# HUB_V1_3_22_0712.net
KiCad netlist of a schematic drawn in Altium Designer
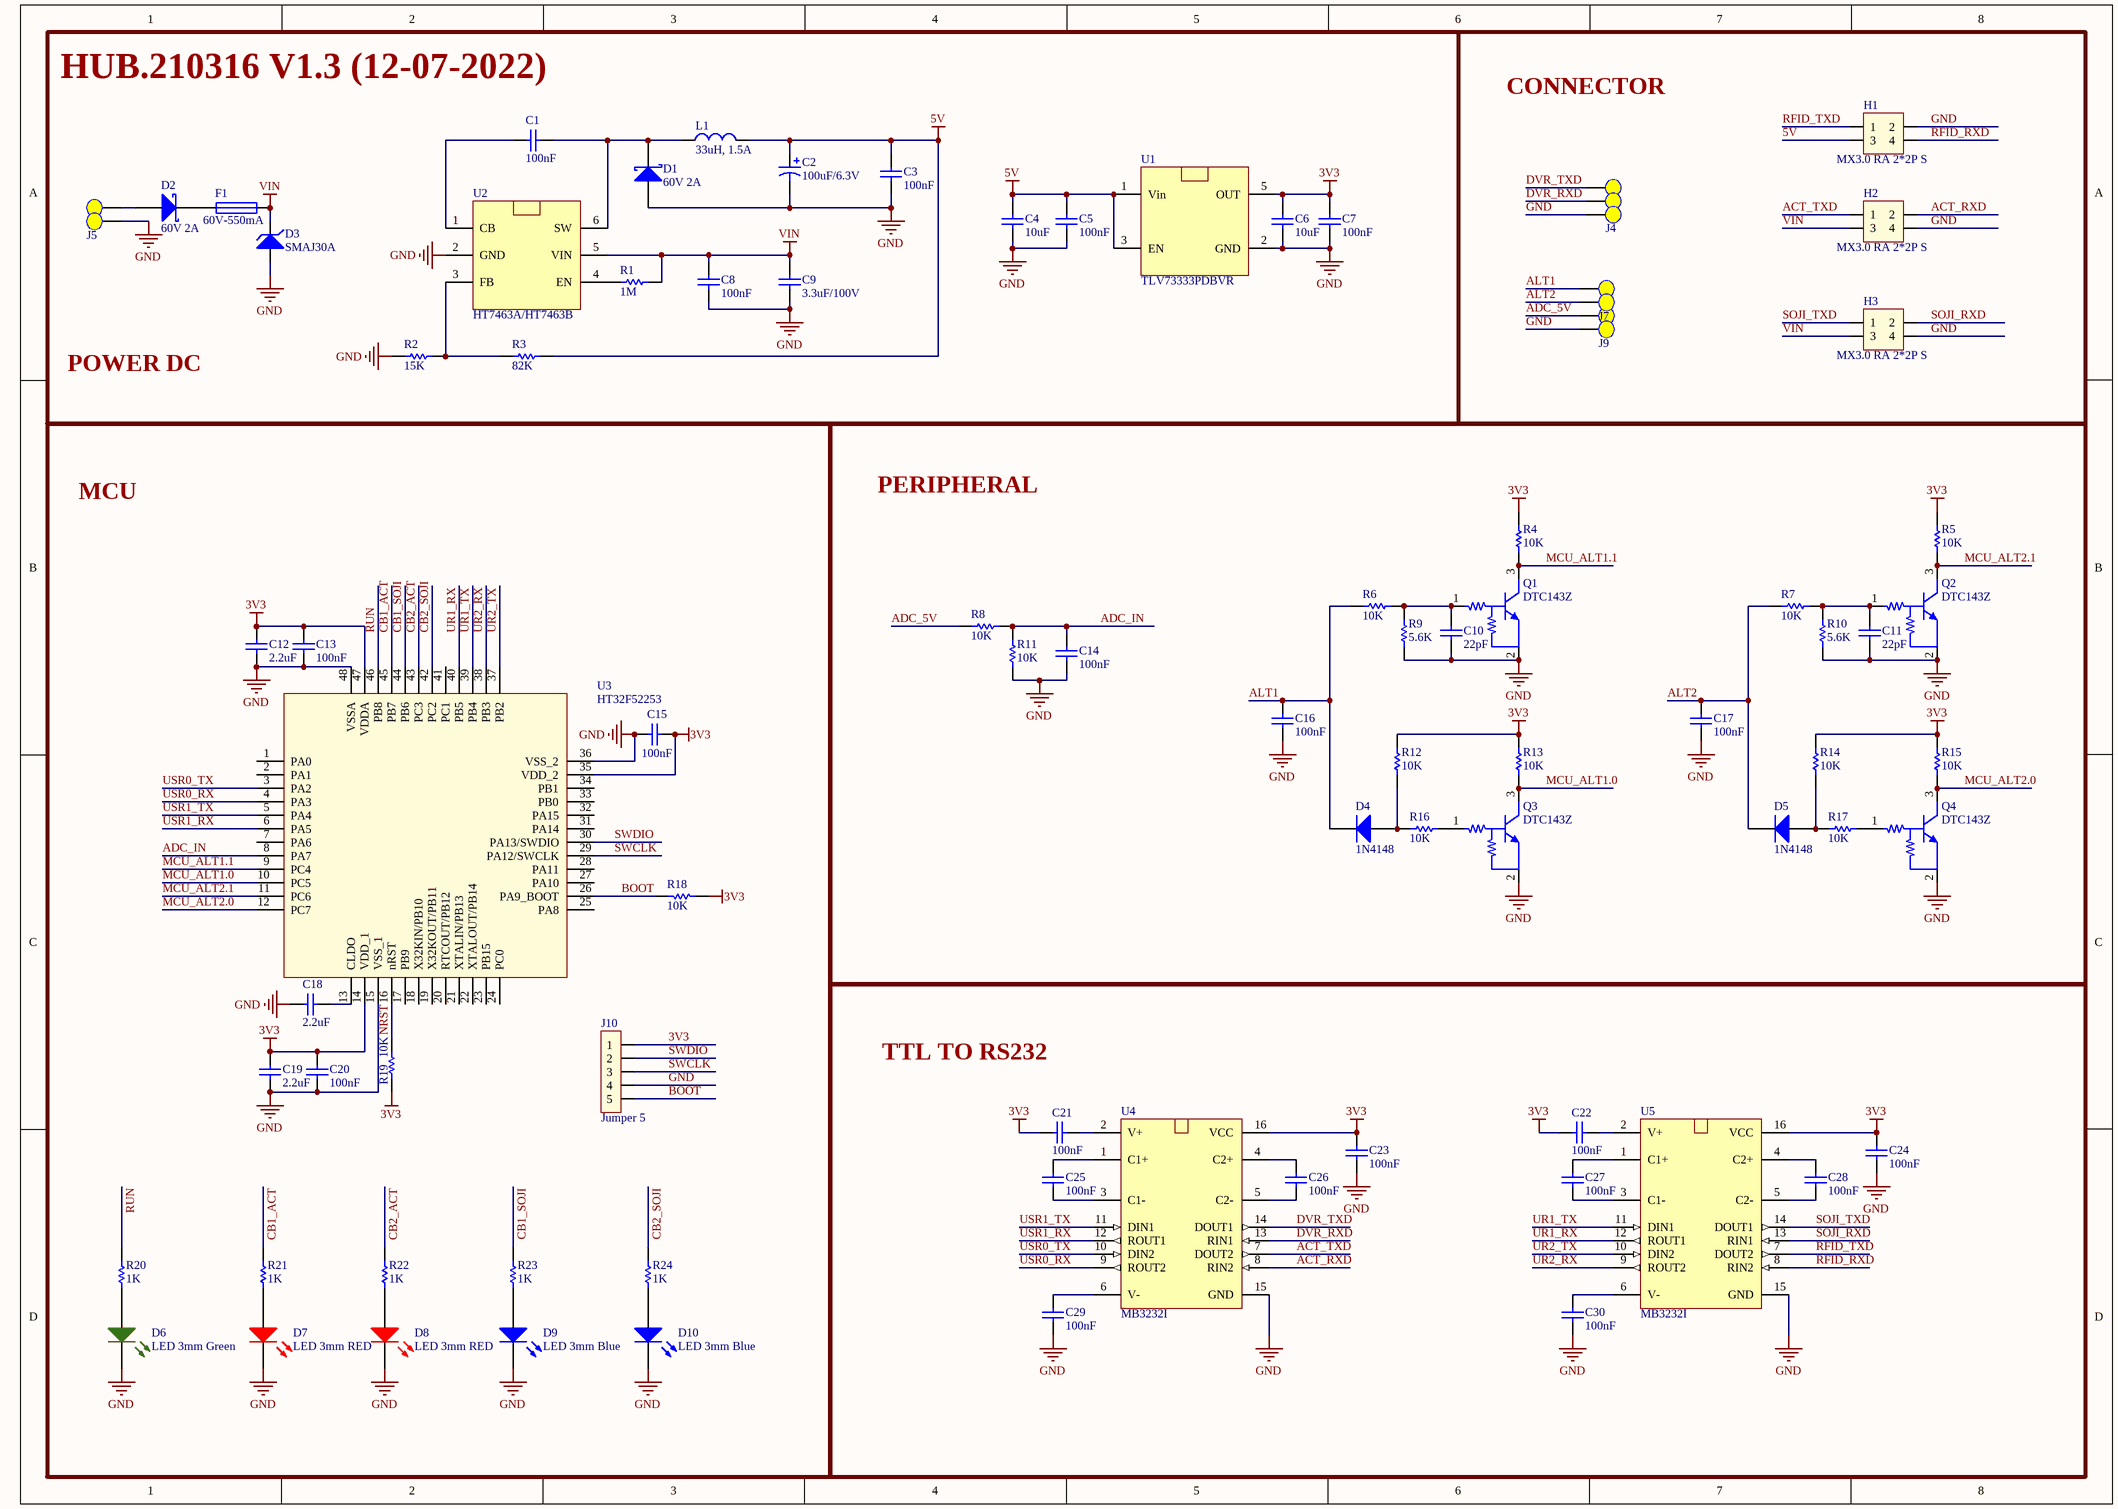
[diagram p0: HUB V1.3.22.0712.SchDoc]

(export (version "E")
  (design (tool "Eeschema 10.0.6"))
  (components
    (comp (ref "C1")
      (value "100nF")
      (footprint "0603 - C")
      (description "CAP CER 100nF 50V C0G/NP0 0603")
      (fields (field (name "MPN") "CL10C104JB8NNNC") (field (name "MFR") "SAMSUNG"))
      (libsource (lib "Library_Chip1") (part "Cap 0603 100nF"))
    )
    (comp (ref "C2")
      (value "100uF/6.3V")
      (footprint "3528 - TANTALUM")
      (description "CAP TANT 100UF 6.3V 10% 1411")
      (fields (field (name "MPN") "T491B107K006AT") (field (name "MFR") "Kemet"))
      (libsource (lib "Library_Chip1") (part "Cap Tan 3528 100uF/6.3V"))
    )
    (comp (ref "C3")
      (value "100nF")
      (footprint "0603 - C")
      (description "CAP CER 100nF 50V C0G/NP0 0603")
      (fields (field (name "MPN") "CL10C104JB8NNNC") (field (name "MFR") "SAMSUNG"))
      (libsource (lib "Library_Chip1") (part "Cap 0603 100nF"))
    )
    (comp (ref "C4")
      (value "10uF")
      (footprint "0603 - C")
      (description "CAP CER 10UF 16V X5R 0603")
      (fields (field (name "MPN") "EMK107BBJ106MA-T") (field (name "MFR") "Yageo"))
      (libsource (lib "Library_Chip") (part "Cap 0603 10uF"))
    )
    (comp (ref "C5")
      (value "100nF")
      (footprint "0603 - C")
      (description "CAP CER 100nF 50V C0G/NP0 0603")
      (fields (field (name "MPN") "CL10C104JB8NNNC") (field (name "MFR") "SAMSUNG"))
      (libsource (lib "Library_Chip") (part "Cap 0603 100nF"))
    )
    (comp (ref "C6")
      (value "10uF")
      (footprint "0603 - C")
      (description "CAP CER 10UF 16V X5R 0603")
      (fields (field (name "MPN") "EMK107BBJ106MA-T") (field (name "MFR") "Yageo"))
      (libsource (lib "Library_Chip") (part "Cap 0603 10uF"))
    )
    (comp (ref "C7")
      (value "100nF")
      (footprint "0603 - C")
      (description "CAP CER 100nF 50V C0G/NP0 0603")
      (fields (field (name "MPN") "CL10C104JB8NNNC") (field (name "MFR") "SAMSUNG"))
      (libsource (lib "Library_Chip") (part "Cap 0603 100nF"))
    )
    (comp (ref "C8")
      (value "100nF")
      (footprint "0603 - C")
      (description "CAP CER 100nF 50V C0G/NP0 0603")
      (fields (field (name "MPN") "CL10C104JB8NNNC") (field (name "MFR") "SAMSUNG"))
      (libsource (lib "Library_Chip1") (part "Cap 0603 100nF"))
    )
    (comp (ref "C9")
      (value "3.3uF/100V")
      (footprint "1210 - C")
      (description "CAP CER 3.3UF 100V X7S 1210")
      (fields (field (name "MPN") "C3225X7S2A335M200AB") (field (name "MFR") "TDK Corporation"))
      (libsource (lib "Library_Chip1") (part "Cap 1210 3.3uF"))
    )
    (comp (ref "C10")
      (value "22pF")
      (footprint "0603 - C")
      (description "CAP CER 22PF 50V C0G/NP0 0603")
      (fields (field (name "MPN") "CL10C220JB8NNNC") (field (name "MFR") "SAMSUNG"))
      (libsource (lib "Library_Chip1") (part "Cap 0603 22pF"))
    )
    (comp (ref "C11")
      (value "22pF")
      (footprint "0603 - C")
      (description "CAP CER 22PF 50V C0G/NP0 0603")
      (fields (field (name "MPN") "CL10C220JB8NNNC") (field (name "MFR") "SAMSUNG"))
      (libsource (lib "Library_Chip1") (part "Cap 0603 22pF"))
    )
    (comp (ref "C12")
      (value "2.2uF")
      (footprint "0603 - C")
      (description "CAP CER 2.2UF 50V X5R 0603")
      (fields (field (name "MFR") "Murata Electronics") (field (name "MPN") "GRM188R61H225KE11J"))
      (libsource (lib "Library_Chip1") (part "Cap 0603 2.2uF"))
    )
    (comp (ref "C13")
      (value "100nF")
      (footprint "0603 - C")
      (description "CAP CER 100nF 50V C0G/NP0 0603")
      (fields (field (name "MPN") "CL10C104JB8NNNC") (field (name "MFR") "SAMSUNG"))
      (libsource (lib "Library_Chip1") (part "Cap 0603 100nF"))
    )
    (comp (ref "C14")
      (value "100nF")
      (footprint "0603 - C")
      (description "CAP CER 100nF 50V C0G/NP0 0603")
      (fields (field (name "MPN") "CL10C104JB8NNNC") (field (name "MFR") "SAMSUNG"))
      (libsource (lib "Library_Chip") (part "Cap 0603 100nF"))
    )
    (comp (ref "C15")
      (value "100nF")
      (footprint "0603 - C")
      (description "CAP CER 100nF 50V C0G/NP0 0603")
      (fields (field (name "MPN") "CL10C104JB8NNNC") (field (name "MFR") "SAMSUNG"))
      (libsource (lib "Library_Chip1") (part "Cap 0603 100nF"))
    )
    (comp (ref "C16")
      (value "100nF")
      (footprint "0603 - C")
      (description "CAP CER 100nF 50V C0G/NP0 0603")
      (fields (field (name "MPN") "CL10C104JB8NNNC") (field (name "MFR") "SAMSUNG"))
      (libsource (lib "Library_Chip1") (part "Cap 0603 100nF"))
    )
    (comp (ref "C17")
      (value "100nF")
      (footprint "0603 - C")
      (description "CAP CER 100nF 50V C0G/NP0 0603")
      (fields (field (name "MPN") "CL10C104JB8NNNC") (field (name "MFR") "SAMSUNG"))
      (libsource (lib "Library_Chip1") (part "Cap 0603 100nF"))
    )
    (comp (ref "C18")
      (value "2.2uF")
      (footprint "0603 - C")
      (description "CAP CER 2.2UF 50V X5R 0603")
      (fields (field (name "MFR") "Murata Electronics") (field (name "MPN") "GRM188R61H225KE11J"))
      (libsource (lib "Library_Chip1") (part "Cap 0603 2.2uF"))
    )
    (comp (ref "C19")
      (value "2.2uF")
      (footprint "0603 - C")
      (description "CAP CER 2.2UF 50V X5R 0603")
      (fields (field (name "MFR") "Murata Electronics") (field (name "MPN") "GRM188R61H225KE11J"))
      (libsource (lib "Library_Chip1") (part "Cap 0603 2.2uF"))
    )
    (comp (ref "C20")
      (value "100nF")
      (footprint "0603 - C")
      (description "CAP CER 100nF 50V C0G/NP0 0603")
      (fields (field (name "MPN") "CL10C104JB8NNNC") (field (name "MFR") "SAMSUNG"))
      (libsource (lib "Library_Chip1") (part "Cap 0603 100nF"))
    )
    (comp (ref "C21")
      (value "100nF")
      (footprint "0603 - C")
      (description "CAP CER 100nF 50V C0G/NP0 0603")
      (fields (field (name "MPN") "CL10C104JB8NNNC") (field (name "MFR") "SAMSUNG"))
      (libsource (lib "Library_Chip") (part "Cap 0603 100nF"))
    )
    (comp (ref "C22")
      (value "100nF")
      (footprint "0603 - C")
      (description "CAP CER 100nF 50V C0G/NP0 0603")
      (fields (field (name "MPN") "CL10C104JB8NNNC") (field (name "MFR") "SAMSUNG"))
      (libsource (lib "Library_Chip") (part "Cap 0603 100nF"))
    )
    (comp (ref "C23")
      (value "100nF")
      (footprint "0603 - C")
      (description "CAP CER 100nF 50V C0G/NP0 0603")
      (fields (field (name "MPN") "CL10C104JB8NNNC") (field (name "MFR") "SAMSUNG"))
      (libsource (lib "Library_Chip") (part "Cap 0603 100nF"))
    )
    (comp (ref "C24")
      (value "100nF")
      (footprint "0603 - C")
      (description "CAP CER 100nF 50V C0G/NP0 0603")
      (fields (field (name "MPN") "CL10C104JB8NNNC") (field (name "MFR") "SAMSUNG"))
      (libsource (lib "Library_Chip") (part "Cap 0603 100nF"))
    )
    (comp (ref "C25")
      (value "100nF")
      (footprint "0603 - C")
      (description "CAP CER 100nF 50V C0G/NP0 0603")
      (fields (field (name "MPN") "CL10C104JB8NNNC") (field (name "MFR") "SAMSUNG"))
      (libsource (lib "Library_Chip") (part "Cap 0603 100nF"))
    )
    (comp (ref "C26")
      (value "100nF")
      (footprint "0603 - C")
      (description "CAP CER 100nF 50V C0G/NP0 0603")
      (fields (field (name "MPN") "CL10C104JB8NNNC") (field (name "MFR") "SAMSUNG"))
      (libsource (lib "Library_Chip") (part "Cap 0603 100nF"))
    )
    (comp (ref "C27")
      (value "100nF")
      (footprint "0603 - C")
      (description "CAP CER 100nF 50V C0G/NP0 0603")
      (fields (field (name "MPN") "CL10C104JB8NNNC") (field (name "MFR") "SAMSUNG"))
      (libsource (lib "Library_Chip") (part "Cap 0603 100nF"))
    )
    (comp (ref "C28")
      (value "100nF")
      (footprint "0603 - C")
      (description "CAP CER 100nF 50V C0G/NP0 0603")
      (fields (field (name "MPN") "CL10C104JB8NNNC") (field (name "MFR") "SAMSUNG"))
      (libsource (lib "Library_Chip") (part "Cap 0603 100nF"))
    )
    (comp (ref "C29")
      (value "100nF")
      (footprint "0603 - C")
      (description "CAP CER 100nF 50V C0G/NP0 0603")
      (fields (field (name "MPN") "CL10C104JB8NNNC") (field (name "MFR") "SAMSUNG"))
      (libsource (lib "Library_Chip") (part "Cap 0603 100nF"))
    )
    (comp (ref "C30")
      (value "100nF")
      (footprint "0603 - C")
      (description "CAP CER 100nF 50V C0G/NP0 0603")
      (fields (field (name "MPN") "CL10C104JB8NNNC") (field (name "MFR") "SAMSUNG"))
      (libsource (lib "Library_Chip") (part "Cap 0603 100nF"))
    )
    (comp (ref "D1")
      (value "60V 2A")
      (footprint "SOD-123")
      (description "DIODE SCHOTTKY 60V 2A SOD123W")
      (fields (field (name "MPN") "PMEG6020ER,115") (field (name "MFR") "NXP"))
      (libsource (lib "Library_Chip") (part "Diode PMEG6020ER"))
    )
    (comp (ref "D2")
      (value "60V 2A")
      (footprint "SOD-123")
      (description "DIODE SCHOTTKY 60V 2A SOD123W")
      (fields (field (name "MPN") "PMEG6020ER,115") (field (name "MFR") "NXP"))
      (libsource (lib "Library_Chip1") (part "Diode PMEG6020ER"))
    )
    (comp (ref "D3")
      (value "SMAJ30A")
      (footprint "Diode - SMA")
      (description "TVS DIODE 30V 48.4V DO214AC")
      (fields (field (name "MFR") "Littelfuse Inc."))
      (libsource (lib "Library_Chip") (part "Diode SMAJ30A"))
    )
    (comp (ref "D4")
      (value "1N4148")
      (footprint "SOD-123")
      (description "DIODE GEN PURP 100V 300MA SOD123")
      (fields (field (name "MPN") "1N4148W-7-F") (field (name "MFR") "DIODES"))
      (libsource (lib "Library_Chip1") (part "Diode 1N4148"))
    )
    (comp (ref "D5")
      (value "1N4148")
      (footprint "SOD-123")
      (description "DIODE GEN PURP 100V 300MA SOD123")
      (fields (field (name "MPN") "1N4148W-7-F") (field (name "MFR") "DIODES"))
      (libsource (lib "Library_Chip1") (part "Diode 1N4148"))
    )
    (comp (ref "D6")
      (value "LED 3mm Green")
      (footprint "LED-3mm GREEN")
      (fields (field (name "MFR") "xx"))
      (libsource (lib "Library_Chip") (part "LED 3mm Green"))
    )
    (comp (ref "D7")
      (value "LED 3mm RED")
      (footprint "LED-3mm RED")
      (fields (field (name "MFR") "xx"))
      (libsource (lib "Library_Chip") (part "LED 3mm RED"))
    )
    (comp (ref "D8")
      (value "LED 3mm RED")
      (footprint "LED-3mm RED")
      (fields (field (name "MFR") "xx"))
      (libsource (lib "Library_Chip") (part "LED 3mm RED"))
    )
    (comp (ref "D9")
      (value "LED 3mm Blue")
      (footprint "LED-3mm BLUE")
      (fields (field (name "MFR") "China") (field (name "MPN") "xx"))
      (libsource (lib "Library_Chip") (part "LED 3mm Blue"))
    )
    (comp (ref "D10")
      (value "LED 3mm Blue")
      (footprint "LED-3mm BLUE")
      (fields (field (name "MFR") "China") (field (name "MPN") "xx"))
      (libsource (lib "Library_Chip") (part "LED 3mm Blue"))
    )
    (comp (ref "F1")
      (value "60V-550mA")
      (footprint "2016 - Fuse")
      (description "PTC Resettable Fuse 60V 550mA")
      (fields (field (name "MFR") "Bourns Inc.") (field (name "MPN") "MF-SMDF050-2"))
      (libsource (lib "Library_Chip") (part "Fuse 60V - 550mA"))
    )
    (comp (ref "H1")
      (value "MX3.0 RA 2*2P S")
      (footprint "43045-M3045-2x2-B")
      (description "Micro-Fit 3.0™ Straight Header, 3.00mm Pitch, Dual Row, 4 Circuits")
      (fields (field (name "MPN") "M3045-2x2-B") (field (name "MFR") "China"))
      (libsource (lib "Library_ Connector") (part "HD2x2 S"))
    )
    (comp (ref "H2")
      (value "MX3.0 RA 2*2P S")
      (footprint "43045-M3045-2x2-B")
      (description "Micro-Fit 3.0™ Straight Header, 3.00mm Pitch, Dual Row, 4 Circuits")
      (fields (field (name "MPN") "M3045-2x2-B") (field (name "MFR") "China"))
      (libsource (lib "Library_ Connector") (part "HD2x2 S"))
    )
    (comp (ref "H3")
      (value "MX3.0 RA 2*2P S")
      (footprint "43045-M3045-2x2-B")
      (description "Micro-Fit 3.0™ Straight Header, 3.00mm Pitch, Dual Row, 4 Circuits")
      (fields (field (name "MPN") "M3045-2x2-B") (field (name "MFR") "China"))
      (libsource (lib "Library_ Connector") (part "HD2x2 S"))
    )
    (comp (ref "J1")
      (value "Test Point")
      (footprint "TP1")
      (description "1mm - 1 layer")
      (libsource (lib "Library_ Connector") (part "TP"))
    )
    (comp (ref "J2")
      (value "Test Point")
      (footprint "TP1")
      (description "1mm - 1 layer")
      (libsource (lib "Library_ Connector") (part "TP"))
    )
    (comp (ref "J3")
      (value "Test Point")
      (footprint "TP1")
      (description "1mm - 1 layer")
      (libsource (lib "Library_ Connector") (part "TP"))
    )
    (comp (ref "J4")
      (value "Test Point")
      (footprint "TP1")
      (description "1mm - 1 layer")
      (libsource (lib "Library_ Connector") (part "TP"))
    )
    (comp (ref "J5")
      (value "Test Point")
      (footprint "TP1")
      (description "1mm - 1 layer")
      (libsource (lib "Library_ Connector") (part "TP"))
    )
    (comp (ref "J6")
      (value "Test Point")
      (footprint "TP1")
      (description "1mm - 1 layer")
      (libsource (lib "Library_ Connector") (part "TP"))
    )
    (comp (ref "J7")
      (value "Test Point")
      (footprint "TP1")
      (description "1mm - 1 layer")
      (libsource (lib "Library_ Connector") (part "TP"))
    )
    (comp (ref "J8")
      (value "Test Point")
      (footprint "TP1")
      (description "1mm - 1 layer")
      (libsource (lib "Library_ Connector") (part "TP"))
    )
    (comp (ref "J9")
      (value "Test Point")
      (footprint "TP1")
      (description "1mm - 1 layer")
      (libsource (lib "Library_ Connector") (part "TP"))
    )
    (comp (ref "J10")
      (value "Jumper 5")
      (footprint "JP5 - 1")
      (description "Jumper 5, 2.54mmx5")
      (libsource (lib "Library_ Connector") (part "JP5"))
    )
    (comp (ref "L1")
      (value "33uH, 1.5A")
      (footprint "INDUCTOR-5D28")
      (description "FIXED IND 33UH 1.5A 286 MOHM SMD")
      (fields (field (name "MPN") "SWPA6028S330MT") (field (name "MFR") "SunLord"))
      (libsource (lib "Library_Chip1") (part "Inductor 33uH, 1.5A"))
    )
    (comp (ref "Q1")
      (value "DTC143Z")
      (footprint "SOT23B")
      (description "TRANS PREBIAS NPN 200MW SMT3")
      (fields (field (name "MPN") "DTC143ZKAT146") (field (name "MFR") "Rohm"))
      (libsource (lib "Library_Chip1") (part "Transistor DTC143Z"))
    )
    (comp (ref "Q2")
      (value "DTC143Z")
      (footprint "SOT23B")
      (description "TRANS PREBIAS NPN 200MW SMT3")
      (fields (field (name "MPN") "DTC143ZKAT146") (field (name "MFR") "Rohm"))
      (libsource (lib "Library_Chip1") (part "Transistor DTC143Z"))
    )
    (comp (ref "Q3")
      (value "DTC143Z")
      (footprint "SOT23B")
      (description "TRANS PREBIAS NPN 200MW SMT3")
      (fields (field (name "MPN") "DTC143ZKAT146") (field (name "MFR") "Rohm"))
      (libsource (lib "Library_Chip1") (part "Transistor DTC143Z"))
    )
    (comp (ref "Q4")
      (value "DTC143Z")
      (footprint "SOT23B")
      (description "TRANS PREBIAS NPN 200MW SMT3")
      (fields (field (name "MPN") "DTC143ZKAT146") (field (name "MFR") "Rohm"))
      (libsource (lib "Library_Chip1") (part "Transistor DTC143Z"))
    )
    (comp (ref "R1")
      (value "1M")
      (footprint "0603 - R")
      (description "RES SMD 1M OHM 1% 1/10W 0603")
      (fields (field (name "MFR") "Yageo") (field (name "MPN") "RC0603FR-071ML"))
      (libsource (lib "Library_Chip1") (part "Res 0603 1M"))
    )
    (comp (ref "R2")
      (value "15K")
      (footprint "0603 - R")
      (description "RES SMD 15K OHM 1% 1/10W 0603")
      (fields (field (name "MFR") "Yageo") (field (name "MPN") "RC0603FR-0715KL"))
      (libsource (lib "Library_Chip1") (part "Res 0603 15K"))
    )
    (comp (ref "R3")
      (value "82K")
      (footprint "0603 - R")
      (description "RES SMD 82K OHM 1% 1/10W 0603")
      (fields (field (name "MFR") "Yageo") (field (name "MPN") "RE0603FRE0782KL"))
      (libsource (lib "Library_Chip1") (part "Res 0603 82K"))
    )
    (comp (ref "R4")
      (value "10K")
      (footprint "0603 - R")
      (description "RES SMD 10K OHM 1% 1/10W 0603")
      (fields (field (name "MFR") "Yageo") (field (name "MPN") "RC0603FR-0710KL"))
      (libsource (lib "Library_Chip1") (part "Res 0603 10K"))
    )
    (comp (ref "R5")
      (value "10K")
      (footprint "0603 - R")
      (description "RES SMD 10K OHM 1% 1/10W 0603")
      (fields (field (name "MFR") "Yageo") (field (name "MPN") "RC0603FR-0710KL"))
      (libsource (lib "Library_Chip1") (part "Res 0603 10K"))
    )
    (comp (ref "R6")
      (value "10K")
      (footprint "0603 - R")
      (description "RES SMD 10K OHM 1% 1/10W 0603")
      (fields (field (name "MFR") "Yageo") (field (name "MPN") "RC0603FR-0710KL"))
      (libsource (lib "Library_Chip1") (part "Res 0603 10K"))
    )
    (comp (ref "R7")
      (value "10K")
      (footprint "0603 - R")
      (description "RES SMD 10K OHM 1% 1/10W 0603")
      (fields (field (name "MFR") "Yageo") (field (name "MPN") "RC0603FR-0710KL"))
      (libsource (lib "Library_Chip1") (part "Res 0603 10K"))
    )
    (comp (ref "R8")
      (value "10K")
      (footprint "0603 - R")
      (description "RES SMD 10K OHM 1% 1/10W 0603")
      (fields (field (name "MFR") "Yageo") (field (name "MPN") "RC0603FR-0710KL"))
      (libsource (lib "Library_Chip1") (part "Res 0603 10K"))
    )
    (comp (ref "R9")
      (value "5.6K")
      (footprint "0603 - R")
      (description "RES SMD 5.6K OHM 1% 1/10W 0603")
      (fields (field (name "MFR") "Yageo") (field (name "MPN") "RC0603FR-075K6L"))
      (libsource (lib "Library_Chip1") (part "Res 0603 5.6K"))
    )
    (comp (ref "R10")
      (value "5.6K")
      (footprint "0603 - R")
      (description "RES SMD 5.6K OHM 1% 1/10W 0603")
      (fields (field (name "MFR") "Yageo") (field (name "MPN") "RC0603FR-075K6L"))
      (libsource (lib "Library_Chip1") (part "Res 0603 5.6K"))
    )
    (comp (ref "R11")
      (value "10K")
      (footprint "0603 - R")
      (description "RES SMD 10K OHM 1% 1/10W 0603")
      (fields (field (name "MFR") "Yageo") (field (name "MPN") "RC0603FR-0710KL"))
      (libsource (lib "Library_Chip1") (part "Res 0603 10K"))
    )
    (comp (ref "R12")
      (value "10K")
      (footprint "0603 - R")
      (description "RES SMD 10K OHM 1% 1/10W 0603")
      (fields (field (name "MFR") "Yageo") (field (name "MPN") "RC0603FR-0710KL"))
      (libsource (lib "Library_Chip1") (part "Res 0603 10K"))
    )
    (comp (ref "R13")
      (value "10K")
      (footprint "0603 - R")
      (description "RES SMD 10K OHM 1% 1/10W 0603")
      (fields (field (name "MFR") "Yageo") (field (name "MPN") "RC0603FR-0710KL"))
      (libsource (lib "Library_Chip1") (part "Res 0603 10K"))
    )
    (comp (ref "R14")
      (value "10K")
      (footprint "0603 - R")
      (description "RES SMD 10K OHM 1% 1/10W 0603")
      (fields (field (name "MFR") "Yageo") (field (name "MPN") "RC0603FR-0710KL"))
      (libsource (lib "Library_Chip1") (part "Res 0603 10K"))
    )
    (comp (ref "R15")
      (value "10K")
      (footprint "0603 - R")
      (description "RES SMD 10K OHM 1% 1/10W 0603")
      (fields (field (name "MFR") "Yageo") (field (name "MPN") "RC0603FR-0710KL"))
      (libsource (lib "Library_Chip1") (part "Res 0603 10K"))
    )
    (comp (ref "R16")
      (value "10K")
      (footprint "0603 - R")
      (description "RES SMD 10K OHM 1% 1/10W 0603")
      (fields (field (name "MFR") "Yageo") (field (name "MPN") "RC0603FR-0710KL"))
      (libsource (lib "Library_Chip1") (part "Res 0603 10K"))
    )
    (comp (ref "R17")
      (value "10K")
      (footprint "0603 - R")
      (description "RES SMD 10K OHM 1% 1/10W 0603")
      (fields (field (name "MFR") "Yageo") (field (name "MPN") "RC0603FR-0710KL"))
      (libsource (lib "Library_Chip1") (part "Res 0603 10K"))
    )
    (comp (ref "R18")
      (value "10K")
      (footprint "0603 - R")
      (description "RES SMD 10K OHM 1% 1/10W 0603")
      (fields (field (name "MFR") "Yageo") (field (name "MPN") "RC0603FR-0710KL"))
      (libsource (lib "Library_Chip") (part "Res 0603 10K"))
    )
    (comp (ref "R19")
      (value "10K")
      (footprint "0603 - R")
      (description "RES SMD 10K OHM 1% 1/10W 0603")
      (fields (field (name "MFR") "Yageo") (field (name "MPN") "RC0603FR-0710KL"))
      (libsource (lib "Library_Chip1") (part "Res 0603 10K"))
    )
    (comp (ref "R20")
      (value "1K")
      (footprint "0603 - R")
      (description "RES SMD 1K OHM 1% 1/10W 0603")
      (fields (field (name "MFR") "Yageo") (field (name "MPN") "RC0603FR-071KL"))
      (libsource (lib "Library_Chip") (part "Res 0603 1K"))
    )
    (comp (ref "R21")
      (value "1K")
      (footprint "0603 - R")
      (description "RES SMD 1K OHM 1% 1/10W 0603")
      (fields (field (name "MFR") "Yageo") (field (name "MPN") "RC0603FR-071KL"))
      (libsource (lib "Library_Chip") (part "Res 0603 1K"))
    )
    (comp (ref "R22")
      (value "1K")
      (footprint "0603 - R")
      (description "RES SMD 1K OHM 1% 1/10W 0603")
      (fields (field (name "MFR") "Yageo") (field (name "MPN") "RC0603FR-071KL"))
      (libsource (lib "Library_Chip") (part "Res 0603 1K"))
    )
    (comp (ref "R23")
      (value "1K")
      (footprint "0603 - R")
      (description "RES SMD 1K OHM 1% 1/10W 0603")
      (fields (field (name "MFR") "Yageo") (field (name "MPN") "RC0603FR-071KL"))
      (libsource (lib "Library_Chip") (part "Res 0603 1K"))
    )
    (comp (ref "R24")
      (value "1K")
      (footprint "0603 - R")
      (description "RES SMD 1K OHM 1% 1/10W 0603")
      (fields (field (name "MFR") "Yageo") (field (name "MPN") "RC0603FR-071KL"))
      (libsource (lib "Library_Chip") (part "Res 0603 1K"))
    )
    (comp (ref "U1")
      (value "TLV73333PDBVR")
      (footprint "SOT23-5")
      (description "IC REG LINEAR 3.3V 300MA SOT23-5")
      (fields (field (name "MFR") "TI"))
      (libsource (lib "Library_IC") (part "TLV73333PDBVR"))
    )
    (comp (ref "U2")
      (value "HT7463A/HT7463B")
      (footprint "SOT23-6_L")
      (description "52V/600mA, 1.25MHz/550kHz\r\nAsynchronous Step Down Converter")
      (fields (field (name "MFR") "Holtek"))
      (libsource (lib "Library_IC") (part "HT7463A/HT7463B"))
    )
    (comp (ref "U3")
      (value "HT32F52253")
      (footprint "LQFP48")
      (description "HT32F52253 48 LQFP-A")
      (fields (field (name "MFR") "Holtek"))
      (libsource (lib "Library_IC") (part "HT32F52253 48 LQFP-A"))
    )
    (comp (ref "U4")
      (value "MB3232I")
      (footprint "TSSOP16")
      (description "IC DRVR/RCVR MLTCH RS232 16TSSOP")
      (fields (field (name "MPN") "MAX3232IPWR") (field (name "MFR") "TI"))
      (libsource (lib "Library_IC") (part "MAX3232IPW"))
    )
    (comp (ref "U5")
      (value "MB3232I")
      (footprint "TSSOP16")
      (description "IC DRVR/RCVR MLTCH RS232 16TSSOP")
      (fields (field (name "MPN") "MAX3232IPWR") (field (name "MFR") "TI"))
      (libsource (lib "Library_IC") (part "MAX3232IPW"))
    )
  )
  (nets
    (net (code "1") (name "/ACT_RXD") (class "Default")
      (node (ref "H2") (pin "2") (pinfunction "2_2") (pintype "passive"))
      (node (ref "U4") (pin "8") (pinfunction "RIN2_8") (pintype "input"))
    )
    (net (code "2") (name "/ACT_TXD") (class "Default")
      (node (ref "H2") (pin "1") (pinfunction "1_1") (pintype "passive"))
      (node (ref "U4") (pin "7") (pinfunction "DOUT2_7") (pintype "output"))
    )
    (net (code "3") (name "/ADC_5V") (class "Default")
      (node (ref "J8") (pin "1") (pinfunction "1_1") (pintype "power_in"))
      (node (ref "R8") (pin "2") (pinfunction "2_2") (pintype "passive"))
    )
    (net (code "4") (name "/ADC_IN") (class "Default")
      (node (ref "C14") (pin "2") (pinfunction "2_2") (pintype "passive"))
      (node (ref "R11") (pin "2") (pinfunction "2_2") (pintype "passive"))
      (node (ref "R8") (pin "1") (pinfunction "1_1") (pintype "passive"))
      (node (ref "U3") (pin "8") (pinfunction "PA7_8") (pintype "passive"))
    )
    (net (code "5") (name "/ALT1") (class "Default")
      (node (ref "C16") (pin "2") (pinfunction "2_2") (pintype "passive"))
      (node (ref "D4") (pin "2") (pinfunction "K_2") (pintype "passive"))
      (node (ref "J6") (pin "1") (pinfunction "1_1") (pintype "power_in"))
      (node (ref "R6") (pin "1") (pinfunction "1_1") (pintype "passive"))
    )
    (net (code "6") (name "/ALT2") (class "Default")
      (node (ref "C17") (pin "2") (pinfunction "2_2") (pintype "passive"))
      (node (ref "D5") (pin "2") (pinfunction "K_2") (pintype "passive"))
      (node (ref "J7") (pin "1") (pinfunction "1_1") (pintype "power_in"))
      (node (ref "R7") (pin "1") (pinfunction "1_1") (pintype "passive"))
    )
    (net (code "7") (name "/BOOT") (class "Default")
      (node (ref "J10") (pin "5") (pinfunction "5_5") (pintype "passive"))
      (node (ref "R18") (pin "2") (pinfunction "2_2") (pintype "passive"))
      (node (ref "U3") (pin "26") (pinfunction "PA9_BOOT_26") (pintype "passive"))
    )
    (net (code "8") (name "/CB1_ACT") (class "Default")
      (node (ref "R21") (pin "1") (pinfunction "1_1") (pintype "passive"))
      (node (ref "U3") (pin "45") (pinfunction "PB7_45") (pintype "passive"))
    )
    (net (code "9") (name "/CB1_SOJI") (class "Default")
      (node (ref "R23") (pin "1") (pinfunction "1_1") (pintype "passive"))
      (node (ref "U3") (pin "44") (pinfunction "PB6_44") (pintype "passive"))
    )
    (net (code "10") (name "/CB2_ACT") (class "Default")
      (node (ref "R22") (pin "1") (pinfunction "1_1") (pintype "passive"))
      (node (ref "U3") (pin "43") (pinfunction "PC3_43") (pintype "passive"))
    )
    (net (code "11") (name "/CB2_SOJI") (class "Default")
      (node (ref "R24") (pin "1") (pinfunction "1_1") (pintype "passive"))
      (node (ref "U3") (pin "42") (pinfunction "PC2_42") (pintype "passive"))
    )
    (net (code "12") (name "/DVR_RXD") (class "Default")
      (node (ref "J2") (pin "1") (pinfunction "1_1") (pintype "power_in"))
      (node (ref "U4") (pin "13") (pinfunction "RIN1_13") (pintype "input"))
    )
    (net (code "13") (name "/DVR_TXD") (class "Default")
      (node (ref "J1") (pin "1") (pinfunction "1_1") (pintype "power_in"))
      (node (ref "U4") (pin "14") (pinfunction "DOUT1_14") (pintype "output"))
    )
    (net (code "14") (name "/MCU_ALT1.0") (class "Default")
      (node (ref "Q3") (pin "3") (pinfunction "OUT_3") (pintype "passive"))
      (node (ref "R13") (pin "1") (pinfunction "1_1") (pintype "passive"))
      (node (ref "U3") (pin "10") (pinfunction "PC5_10") (pintype "passive"))
    )
    (net (code "15") (name "/MCU_ALT1.1") (class "Default")
      (node (ref "Q1") (pin "3") (pinfunction "OUT_3") (pintype "passive"))
      (node (ref "R4") (pin "1") (pinfunction "1_1") (pintype "passive"))
      (node (ref "U3") (pin "9") (pinfunction "PC4_9") (pintype "passive"))
    )
    (net (code "16") (name "/MCU_ALT2.0") (class "Default")
      (node (ref "Q4") (pin "3") (pinfunction "OUT_3") (pintype "passive"))
      (node (ref "R15") (pin "1") (pinfunction "1_1") (pintype "passive"))
      (node (ref "U3") (pin "12") (pinfunction "PC7_12") (pintype "passive"))
    )
    (net (code "17") (name "/MCU_ALT2.1") (class "Default")
      (node (ref "Q2") (pin "3") (pinfunction "OUT_3") (pintype "passive"))
      (node (ref "R5") (pin "1") (pinfunction "1_1") (pintype "passive"))
      (node (ref "U3") (pin "11") (pinfunction "PC6_11") (pintype "passive"))
    )
    (net (code "18") (name "/NRST") (class "Default")
      (node (ref "R19") (pin "2") (pinfunction "2_2") (pintype "passive"))
      (node (ref "U3") (pin "16") (pinfunction "nRST_16") (pintype "passive"))
    )
    (net (code "19") (name "/RFID_RXD") (class "Default")
      (node (ref "H1") (pin "4") (pinfunction "4_4") (pintype "passive"))
      (node (ref "U5") (pin "8") (pinfunction "RIN2_8") (pintype "input"))
    )
    (net (code "20") (name "/RFID_TXD") (class "Default")
      (node (ref "H1") (pin "1") (pinfunction "1_1") (pintype "passive"))
      (node (ref "U5") (pin "7") (pinfunction "DOUT2_7") (pintype "output"))
    )
    (net (code "21") (name "/RUN") (class "Default")
      (node (ref "R20") (pin "1") (pinfunction "1_1") (pintype "passive"))
      (node (ref "U3") (pin "46") (pinfunction "PB8_46") (pintype "passive"))
    )
    (net (code "22") (name "/SOJI_RXD") (class "Default")
      (node (ref "H3") (pin "2") (pinfunction "2_2") (pintype "passive"))
      (node (ref "U5") (pin "13") (pinfunction "RIN1_13") (pintype "input"))
    )
    (net (code "23") (name "/SOJI_TXD") (class "Default")
      (node (ref "H3") (pin "1") (pinfunction "1_1") (pintype "passive"))
      (node (ref "U5") (pin "14") (pinfunction "DOUT1_14") (pintype "output"))
    )
    (net (code "24") (name "/SWCLK") (class "Default")
      (node (ref "J10") (pin "3") (pinfunction "3_3") (pintype "passive"))
      (node (ref "U3") (pin "29") (pinfunction "PA12/SWCLK_29") (pintype "passive"))
    )
    (net (code "25") (name "/SWDIO") (class "Default")
      (node (ref "J10") (pin "2") (pinfunction "2_2") (pintype "passive"))
      (node (ref "U3") (pin "30") (pinfunction "PA13/SWDIO_30") (pintype "passive"))
    )
    (net (code "26") (name "/UR1_RX") (class "Default")
      (node (ref "U3") (pin "40") (pinfunction "PB5_40") (pintype "passive"))
      (node (ref "U5") (pin "12") (pinfunction "ROUT1_12") (pintype "output"))
    )
    (net (code "27") (name "/UR1_TX") (class "Default")
      (node (ref "U3") (pin "39") (pinfunction "PB4_39") (pintype "passive"))
      (node (ref "U5") (pin "11") (pinfunction "DIN1_11") (pintype "input"))
    )
    (net (code "28") (name "/UR2_RX") (class "Default")
      (node (ref "U3") (pin "38") (pinfunction "PB3_38") (pintype "passive"))
      (node (ref "U5") (pin "9") (pinfunction "ROUT2_9") (pintype "output"))
    )
    (net (code "29") (name "/UR2_TX") (class "Default")
      (node (ref "U3") (pin "37") (pinfunction "PB2_37") (pintype "passive"))
      (node (ref "U5") (pin "10") (pinfunction "DIN2_10") (pintype "input"))
    )
    (net (code "30") (name "/USR0_RX") (class "Default")
      (node (ref "U3") (pin "4") (pinfunction "PA3_4") (pintype "passive"))
      (node (ref "U4") (pin "9") (pinfunction "ROUT2_9") (pintype "output"))
    )
    (net (code "31") (name "/USR0_TX") (class "Default")
      (node (ref "U3") (pin "3") (pinfunction "PA2_3") (pintype "passive"))
      (node (ref "U4") (pin "10") (pinfunction "DIN2_10") (pintype "input"))
    )
    (net (code "32") (name "/USR1_RX") (class "Default")
      (node (ref "U3") (pin "6") (pinfunction "PA5_6") (pintype "passive"))
      (node (ref "U4") (pin "12") (pinfunction "ROUT1_12") (pintype "output"))
    )
    (net (code "33") (name "/USR1_TX") (class "Default")
      (node (ref "U3") (pin "5") (pinfunction "PA4_5") (pintype "passive"))
      (node (ref "U4") (pin "11") (pinfunction "DIN1_11") (pintype "input"))
    )
    (net (code "34") (name "3V3") (class "Default")
      (node (ref "C12") (pin "2") (pinfunction "2_2") (pintype "passive"))
      (node (ref "C13") (pin "1") (pinfunction "1_1") (pintype "passive"))
      (node (ref "C15") (pin "2") (pinfunction "2_2") (pintype "passive"))
      (node (ref "C19") (pin "2") (pinfunction "2_2") (pintype "passive"))
      (node (ref "C20") (pin "1") (pinfunction "1_1") (pintype "passive"))
      (node (ref "C21") (pin "2") (pinfunction "2_2") (pintype "passive"))
      (node (ref "C22") (pin "2") (pinfunction "2_2") (pintype "passive"))
      (node (ref "C23") (pin "1") (pinfunction "1_1") (pintype "passive"))
      (node (ref "C24") (pin "1") (pinfunction "1_1") (pintype "passive"))
      (node (ref "C6") (pin "2") (pinfunction "2_2") (pintype "passive"))
      (node (ref "C7") (pin "2") (pinfunction "2_2") (pintype "passive"))
      (node (ref "J10") (pin "1") (pinfunction "1_1") (pintype "passive"))
      (node (ref "R12") (pin "2") (pinfunction "2_2") (pintype "passive"))
      (node (ref "R13") (pin "2") (pinfunction "2_2") (pintype "passive"))
      (node (ref "R14") (pin "2") (pinfunction "2_2") (pintype "passive"))
      (node (ref "R15") (pin "2") (pinfunction "2_2") (pintype "passive"))
      (node (ref "R18") (pin "1") (pinfunction "1_1") (pintype "passive"))
      (node (ref "R19") (pin "1") (pinfunction "1_1") (pintype "passive"))
      (node (ref "R4") (pin "2") (pinfunction "2_2") (pintype "passive"))
      (node (ref "R5") (pin "2") (pinfunction "2_2") (pintype "passive"))
      (node (ref "U1") (pin "5") (pinfunction "OUT_5") (pintype "passive"))
      (node (ref "U3") (pin "14") (pinfunction "VDD_1_14") (pintype "passive"))
      (node (ref "U3") (pin "35") (pinfunction "VDD_2_35") (pintype "passive"))
      (node (ref "U3") (pin "47") (pinfunction "VDDA_47") (pintype "passive"))
      (node (ref "U4") (pin "16") (pinfunction "VCC_16") (pintype "power_in"))
      (node (ref "U5") (pin "16") (pinfunction "VCC_16") (pintype "power_in"))
    )
    (net (code "35") (name "5V") (class "Default")
      (node (ref "C2") (pin "1") (pinfunction "1_1") (pintype "passive"))
      (node (ref "C3") (pin "2") (pinfunction "2_2") (pintype "passive"))
      (node (ref "C4") (pin "2") (pinfunction "2_2") (pintype "passive"))
      (node (ref "C5") (pin "2") (pinfunction "2_2") (pintype "passive"))
      (node (ref "H1") (pin "3") (pinfunction "3_3") (pintype "passive"))
      (node (ref "L1") (pin "2") (pinfunction "2_2") (pintype "passive"))
      (node (ref "R3") (pin "2") (pinfunction "2_2") (pintype "passive"))
      (node (ref "U1") (pin "1") (pinfunction "Vin_1") (pintype "passive"))
      (node (ref "U1") (pin "3") (pinfunction "EN_3") (pintype "passive"))
    )
    (net (code "36") (name "GND") (class "Default")
      (node (ref "C10") (pin "1") (pinfunction "1_1") (pintype "passive"))
      (node (ref "C11") (pin "1") (pinfunction "1_1") (pintype "passive"))
      (node (ref "C12") (pin "1") (pinfunction "1_1") (pintype "passive"))
      (node (ref "C13") (pin "2") (pinfunction "2_2") (pintype "passive"))
      (node (ref "C14") (pin "1") (pinfunction "1_1") (pintype "passive"))
      (node (ref "C15") (pin "1") (pinfunction "1_1") (pintype "passive"))
      (node (ref "C16") (pin "1") (pinfunction "1_1") (pintype "passive"))
      (node (ref "C17") (pin "1") (pinfunction "1_1") (pintype "passive"))
      (node (ref "C18") (pin "2") (pinfunction "2_2") (pintype "passive"))
      (node (ref "C19") (pin "1") (pinfunction "1_1") (pintype "passive"))
      (node (ref "C2") (pin "2") (pinfunction "2_2") (pintype "passive"))
      (node (ref "C20") (pin "2") (pinfunction "2_2") (pintype "passive"))
      (node (ref "C23") (pin "2") (pinfunction "2_2") (pintype "passive"))
      (node (ref "C24") (pin "2") (pinfunction "2_2") (pintype "passive"))
      (node (ref "C29") (pin "2") (pinfunction "2_2") (pintype "passive"))
      (node (ref "C3") (pin "1") (pinfunction "1_1") (pintype "passive"))
      (node (ref "C30") (pin "2") (pinfunction "2_2") (pintype "passive"))
      (node (ref "C4") (pin "1") (pinfunction "1_1") (pintype "passive"))
      (node (ref "C5") (pin "1") (pinfunction "1_1") (pintype "passive"))
      (node (ref "C6") (pin "1") (pinfunction "1_1") (pintype "passive"))
      (node (ref "C7") (pin "1") (pinfunction "1_1") (pintype "passive"))
      (node (ref "C8") (pin "1") (pinfunction "1_1") (pintype "passive"))
      (node (ref "C9") (pin "1") (pinfunction "1_1") (pintype "passive"))
      (node (ref "D1") (pin "1") (pinfunction "A_1") (pintype "passive"))
      (node (ref "D10") (pin "2") (pinfunction "K_2") (pintype "passive"))
      (node (ref "D3") (pin "1") (pinfunction "A_1") (pintype "passive"))
      (node (ref "D6") (pin "2") (pinfunction "K_2") (pintype "passive"))
      (node (ref "D7") (pin "2") (pinfunction "K_2") (pintype "passive"))
      (node (ref "D8") (pin "2") (pinfunction "K_2") (pintype "passive"))
      (node (ref "D9") (pin "2") (pinfunction "K_2") (pintype "passive"))
      (node (ref "H1") (pin "2") (pinfunction "2_2") (pintype "passive"))
      (node (ref "H2") (pin "4") (pinfunction "4_4") (pintype "passive"))
      (node (ref "H3") (pin "4") (pinfunction "4_4") (pintype "passive"))
      (node (ref "J10") (pin "4") (pinfunction "4_4") (pintype "passive"))
      (node (ref "J4") (pin "1") (pinfunction "1_1") (pintype "power_in"))
      (node (ref "J5") (pin "1") (pinfunction "1_1") (pintype "power_in"))
      (node (ref "J9") (pin "1") (pinfunction "1_1") (pintype "power_in"))
      (node (ref "Q1") (pin "2") (pinfunction "GND_2") (pintype "passive"))
      (node (ref "Q2") (pin "2") (pinfunction "GND_2") (pintype "passive"))
      (node (ref "Q3") (pin "2") (pinfunction "GND_2") (pintype "passive"))
      (node (ref "Q4") (pin "2") (pinfunction "GND_2") (pintype "passive"))
      (node (ref "R10") (pin "1") (pinfunction "1_1") (pintype "passive"))
      (node (ref "R11") (pin "1") (pinfunction "1_1") (pintype "passive"))
      (node (ref "R2") (pin "2") (pinfunction "2_2") (pintype "passive"))
      (node (ref "R9") (pin "1") (pinfunction "1_1") (pintype "passive"))
      (node (ref "U1") (pin "2") (pinfunction "GND_2") (pintype "passive"))
      (node (ref "U2") (pin "2") (pinfunction "GND_2") (pintype "power_in"))
      (node (ref "U3") (pin "15") (pinfunction "VSS_1_15") (pintype "passive"))
      (node (ref "U3") (pin "36") (pinfunction "VSS_2_36") (pintype "passive"))
      (node (ref "U3") (pin "48") (pinfunction "VSSA_48") (pintype "passive"))
      (node (ref "U4") (pin "15") (pinfunction "GND_15") (pintype "power_in"))
      (node (ref "U5") (pin "15") (pinfunction "GND_15") (pintype "power_in"))
    )
    (net (code "37") (name "Net-(D1-K)") (class "Default")
      (node (ref "C1") (pin "2") (pinfunction "2_2") (pintype "passive"))
      (node (ref "D1") (pin "2") (pinfunction "K_2") (pintype "passive"))
      (node (ref "L1") (pin "1") (pinfunction "1_1") (pintype "passive"))
      (node (ref "U2") (pin "6") (pinfunction "SW_6") (pintype "power_in"))
    )
    (net (code "38") (name "Net-(D2-A)") (class "Default")
      (node (ref "D2") (pin "1") (pinfunction "A_1") (pintype "passive"))
      (node (ref "J3") (pin "1") (pinfunction "1_1") (pintype "power_in"))
    )
    (net (code "39") (name "Net-(D2-K)") (class "Default")
      (node (ref "D2") (pin "2") (pinfunction "K_2") (pintype "passive"))
      (node (ref "F1") (pin "1") (pinfunction "1_1") (pintype "passive"))
    )
    (net (code "40") (name "Net-(D4-A)") (class "Default")
      (node (ref "D4") (pin "1") (pinfunction "A_1") (pintype "passive"))
      (node (ref "R12") (pin "1") (pinfunction "1_1") (pintype "passive"))
      (node (ref "R16") (pin "2") (pinfunction "2_2") (pintype "passive"))
    )
    (net (code "41") (name "Net-(D5-A)") (class "Default")
      (node (ref "D5") (pin "1") (pinfunction "A_1") (pintype "passive"))
      (node (ref "R14") (pin "1") (pinfunction "1_1") (pintype "passive"))
      (node (ref "R17") (pin "2") (pinfunction "2_2") (pintype "passive"))
    )
    (net (code "42") (name "Net-(D6-A)") (class "Default")
      (node (ref "D6") (pin "1") (pinfunction "A_1") (pintype "passive"))
      (node (ref "R20") (pin "2") (pinfunction "2_2") (pintype "passive"))
    )
    (net (code "43") (name "Net-(D7-A)") (class "Default")
      (node (ref "D7") (pin "1") (pinfunction "A_1") (pintype "passive"))
      (node (ref "R21") (pin "2") (pinfunction "2_2") (pintype "passive"))
    )
    (net (code "44") (name "Net-(D8-A)") (class "Default")
      (node (ref "D8") (pin "1") (pinfunction "A_1") (pintype "passive"))
      (node (ref "R22") (pin "2") (pinfunction "2_2") (pintype "passive"))
    )
    (net (code "45") (name "Net-(D9-A)") (class "Default")
      (node (ref "D9") (pin "1") (pinfunction "A_1") (pintype "passive"))
      (node (ref "R23") (pin "2") (pinfunction "2_2") (pintype "passive"))
    )
    (net (code "46") (name "Net-(D10-A)") (class "Default")
      (node (ref "D10") (pin "1") (pinfunction "A_1") (pintype "passive"))
      (node (ref "R24") (pin "2") (pinfunction "2_2") (pintype "passive"))
    )
    (net (code "47") (name "Net-(Q1-IN)") (class "Default")
      (node (ref "C10") (pin "2") (pinfunction "2_2") (pintype "passive"))
      (node (ref "Q1") (pin "1") (pinfunction "IN_1") (pintype "passive"))
      (node (ref "R6") (pin "2") (pinfunction "2_2") (pintype "passive"))
      (node (ref "R9") (pin "2") (pinfunction "2_2") (pintype "passive"))
    )
    (net (code "48") (name "Net-(Q2-IN)") (class "Default")
      (node (ref "C11") (pin "2") (pinfunction "2_2") (pintype "passive"))
      (node (ref "Q2") (pin "1") (pinfunction "IN_1") (pintype "passive"))
      (node (ref "R10") (pin "2") (pinfunction "2_2") (pintype "passive"))
      (node (ref "R7") (pin "2") (pinfunction "2_2") (pintype "passive"))
    )
    (net (code "49") (name "Net-(Q3-IN)") (class "Default")
      (node (ref "Q3") (pin "1") (pinfunction "IN_1") (pintype "passive"))
      (node (ref "R16") (pin "1") (pinfunction "1_1") (pintype "passive"))
    )
    (net (code "50") (name "Net-(Q4-IN)") (class "Default")
      (node (ref "Q4") (pin "1") (pinfunction "IN_1") (pintype "passive"))
      (node (ref "R17") (pin "1") (pinfunction "1_1") (pintype "passive"))
    )
    (net (code "51") (name "Net-(U2-CB)") (class "Default")
      (node (ref "C1") (pin "1") (pinfunction "1_1") (pintype "passive"))
      (node (ref "U2") (pin "1") (pinfunction "CB_1") (pintype "power_in"))
    )
    (net (code "52") (name "Net-(U2-EN)") (class "Default")
      (node (ref "R1") (pin "2") (pinfunction "2_2") (pintype "passive"))
      (node (ref "U2") (pin "4") (pinfunction "EN_4") (pintype "power_in"))
    )
    (net (code "53") (name "Net-(U2-FB)") (class "Default")
      (node (ref "R2") (pin "1") (pinfunction "1_1") (pintype "passive"))
      (node (ref "R3") (pin "1") (pinfunction "1_1") (pintype "passive"))
      (node (ref "U2") (pin "3") (pinfunction "FB_3") (pintype "power_in"))
    )
    (net (code "54") (name "Net-(U3-CLDO)") (class "Default")
      (node (ref "C18") (pin "1") (pinfunction "1_1") (pintype "passive"))
      (node (ref "U3") (pin "13") (pinfunction "CLDO_13") (pintype "passive"))
    )
    (net (code "55") (name "Net-(U4-C1+)") (class "Default")
      (node (ref "C25") (pin "1") (pinfunction "1_1") (pintype "passive"))
      (node (ref "U4") (pin "1") (pinfunction "C1+_1") (pintype "power_in"))
    )
    (net (code "56") (name "Net-(U4-C1-)") (class "Default")
      (node (ref "C25") (pin "2") (pinfunction "2_2") (pintype "passive"))
      (node (ref "U4") (pin "3") (pinfunction "C1-_3") (pintype "power_in"))
    )
    (net (code "57") (name "Net-(U4-C2+)") (class "Default")
      (node (ref "C26") (pin "1") (pinfunction "1_1") (pintype "passive"))
      (node (ref "U4") (pin "4") (pinfunction "C2+_4") (pintype "power_in"))
    )
    (net (code "58") (name "Net-(U4-C2-)") (class "Default")
      (node (ref "C26") (pin "2") (pinfunction "2_2") (pintype "passive"))
      (node (ref "U4") (pin "5") (pinfunction "C2-_5") (pintype "power_in"))
    )
    (net (code "59") (name "Net-(U4-V+)") (class "Default")
      (node (ref "C21") (pin "1") (pinfunction "1_1") (pintype "passive"))
      (node (ref "U4") (pin "2") (pinfunction "V+_2") (pintype "power_in"))
    )
    (net (code "60") (name "Net-(U4-V-)") (class "Default")
      (node (ref "C29") (pin "1") (pinfunction "1_1") (pintype "passive"))
      (node (ref "U4") (pin "6") (pinfunction "V-_6") (pintype "power_in"))
    )
    (net (code "61") (name "Net-(U5-C1+)") (class "Default")
      (node (ref "C27") (pin "1") (pinfunction "1_1") (pintype "passive"))
      (node (ref "U5") (pin "1") (pinfunction "C1+_1") (pintype "power_in"))
    )
    (net (code "62") (name "Net-(U5-C1-)") (class "Default")
      (node (ref "C27") (pin "2") (pinfunction "2_2") (pintype "passive"))
      (node (ref "U5") (pin "3") (pinfunction "C1-_3") (pintype "power_in"))
    )
    (net (code "63") (name "Net-(U5-C2+)") (class "Default")
      (node (ref "C28") (pin "1") (pinfunction "1_1") (pintype "passive"))
      (node (ref "U5") (pin "4") (pinfunction "C2+_4") (pintype "power_in"))
    )
    (net (code "64") (name "Net-(U5-C2-)") (class "Default")
      (node (ref "C28") (pin "2") (pinfunction "2_2") (pintype "passive"))
      (node (ref "U5") (pin "5") (pinfunction "C2-_5") (pintype "power_in"))
    )
    (net (code "65") (name "Net-(U5-V+)") (class "Default")
      (node (ref "C22") (pin "1") (pinfunction "1_1") (pintype "passive"))
      (node (ref "U5") (pin "2") (pinfunction "V+_2") (pintype "power_in"))
    )
    (net (code "66") (name "Net-(U5-V-)") (class "Default")
      (node (ref "C30") (pin "1") (pinfunction "1_1") (pintype "passive"))
      (node (ref "U5") (pin "6") (pinfunction "V-_6") (pintype "power_in"))
    )
    (net (code "67") (name "VIN") (class "Default")
      (node (ref "C8") (pin "2") (pinfunction "2_2") (pintype "passive"))
      (node (ref "C9") (pin "2") (pinfunction "2_2") (pintype "passive"))
      (node (ref "D3") (pin "2") (pinfunction "K_2") (pintype "passive"))
      (node (ref "F1") (pin "2") (pinfunction "2_2") (pintype "passive"))
      (node (ref "H2") (pin "3") (pinfunction "3_3") (pintype "passive"))
      (node (ref "H3") (pin "3") (pinfunction "3_3") (pintype "passive"))
      (node (ref "R1") (pin "1") (pinfunction "1_1") (pintype "passive"))
      (node (ref "U2") (pin "5") (pinfunction "VIN_5") (pintype "power_in"))
    )
    (net (code "68") (name "unconnected-(U1-NC-Pad4)") (class "Default")
      (node (ref "U1") (pin "4") (pinfunction "NC_4") (pintype "passive"))
    )
    (net (code "69") (name "unconnected-(U3-PA0-Pad1)") (class "Default")
      (node (ref "U3") (pin "1") (pinfunction "PA0_1") (pintype "passive"))
    )
    (net (code "70") (name "unconnected-(U3-PA1-Pad2)") (class "Default")
      (node (ref "U3") (pin "2") (pinfunction "PA1_2") (pintype "passive"))
    )
    (net (code "71") (name "unconnected-(U3-PA6-Pad7)") (class "Default")
      (node (ref "U3") (pin "7") (pinfunction "PA6_7") (pintype "passive"))
    )
    (net (code "72") (name "unconnected-(U3-PA8-Pad25)") (class "Default")
      (node (ref "U3") (pin "25") (pinfunction "PA8_25") (pintype "passive"))
    )
    (net (code "73") (name "unconnected-(U3-PA10-Pad27)") (class "Default")
      (node (ref "U3") (pin "27") (pinfunction "PA10_27") (pintype "passive"))
    )
    (net (code "74") (name "unconnected-(U3-PA11-Pad28)") (class "Default")
      (node (ref "U3") (pin "28") (pinfunction "PA11_28") (pintype "passive"))
    )
    (net (code "75") (name "unconnected-(U3-PA14-Pad31)") (class "Default")
      (node (ref "U3") (pin "31") (pinfunction "PA14_31") (pintype "passive"))
    )
    (net (code "76") (name "unconnected-(U3-PA15-Pad32)") (class "Default")
      (node (ref "U3") (pin "32") (pinfunction "PA15_32") (pintype "passive"))
    )
    (net (code "77") (name "unconnected-(U3-PB0-Pad33)") (class "Default")
      (node (ref "U3") (pin "33") (pinfunction "PB0_33") (pintype "passive"))
    )
    (net (code "78") (name "unconnected-(U3-PB1-Pad34)") (class "Default")
      (node (ref "U3") (pin "34") (pinfunction "PB1_34") (pintype "passive"))
    )
    (net (code "79") (name "unconnected-(U3-PB9-Pad17)") (class "Default")
      (node (ref "U3") (pin "17") (pinfunction "PB9_17") (pintype "passive"))
    )
    (net (code "80") (name "unconnected-(U3-PB15-Pad23)") (class "Default")
      (node (ref "U3") (pin "23") (pinfunction "PB15_23") (pintype "passive"))
    )
    (net (code "81") (name "unconnected-(U3-PC0-Pad24)") (class "Default")
      (node (ref "U3") (pin "24") (pinfunction "PC0_24") (pintype "passive"))
    )
    (net (code "82") (name "unconnected-(U3-PC1-Pad41)") (class "Default")
      (node (ref "U3") (pin "41") (pinfunction "PC1_41") (pintype "passive"))
    )
    (net (code "83") (name "unconnected-(U3-RTCOUT{slash}PB12-Pad20)") (class "Default")
      (node (ref "U3") (pin "20") (pinfunction "RTCOUT/PB12_20") (pintype "passive"))
    )
    (net (code "84") (name "unconnected-(U3-X32KIN{slash}PB10-Pad18)") (class "Default")
      (node (ref "U3") (pin "18") (pinfunction "X32KIN/PB10_18") (pintype "passive"))
    )
    (net (code "85") (name "unconnected-(U3-X32KOUT{slash}PB11-Pad19)") (class "Default")
      (node (ref "U3") (pin "19") (pinfunction "X32KOUT/PB11_19") (pintype "passive"))
    )
    (net (code "86") (name "unconnected-(U3-XTALIN{slash}PB13-Pad21)") (class "Default")
      (node (ref "U3") (pin "21") (pinfunction "XTALIN/PB13_21") (pintype "passive"))
    )
    (net (code "87") (name "unconnected-(U3-XTALOUT{slash}PB14-Pad22)") (class "Default")
      (node (ref "U3") (pin "22") (pinfunction "XTALOUT/PB14_22") (pintype "passive"))
    )
  )
)
